# usb_port.net
KiCad netlist of a schematic drawn in Altium Designer
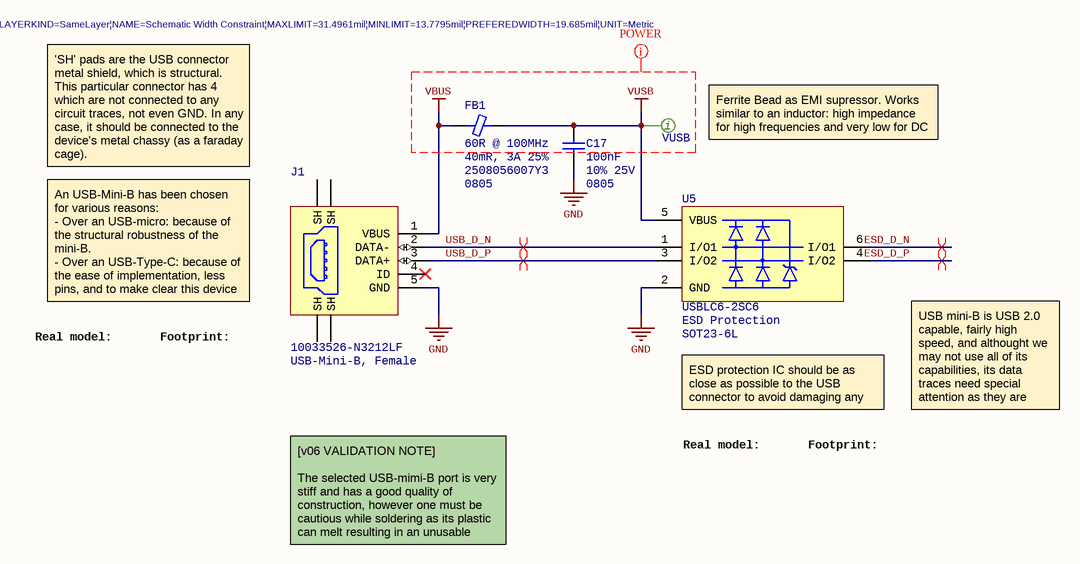
[diagram p0: usb_port.SchDoc]

(export (version "E")
  (design (tool "Eeschema 10.0.6"))
  (components
    (comp (ref "C17")
      (value "100nF")
      (footprint "CAP 0805_2012")
      (description "Ceramic cap size 0805")
      (fields
        (field (name "TOLERANCE") "10% 25V")
        (field (name "PACKAGEDESCRIPTION") "0805")
        (field (name "Comment") "Cap_cer_0805")
      )
      (libsource (lib "tik_handheld_schlib") (part "Cap_cer_0805_100nF_10%"))
    )
    (comp (ref "FB1")
      (value "40mR, 3A 25%")
      (footprint "FER 0805_2012")
      (description "0805, 60Ω, 3A, 25% SMT")
      (fields
        (field (name "DESC") "60R @ 100MHz")
        (field (name "PART") "2508056007Y3")
        (field (name "PACKAGEDESCRIPTION") "0805")
        (field (name "Comment") "Ferrite Bead Chip Fair-Rite 2508056007Y3")
      )
      (libsource (lib "tik_handheld_schlib") (part "Ferrite Bead Chip Fair-Rite 2508056007Y3"))
    )
    (comp (ref "J1")
      (value "USB-MINI-B Female")
      (footprint "FCI USB Type B Mini 10033526-N3212LF")
      (description "USB-MINI-B Female, Manufacturer PN/ID: 10033526-N3212LF")
      (fields
        (field (name "PACKAGEDESCRIPTION") "USB-Mini-B, Female")
        (field (name "PART") "10033526-N3212LF")
      )
      (libsource (lib "tik_handheld_schlib") (part "CON USB-MINI-B Female"))
    )
    (comp (ref "U5")
      (value "IC USBLC6-2SC6 ESD Prot")
      (footprint "SOT-23-6L USBLC6-2SC6")
      (description "Very low capacitance ESD protection")
      (fields
        (field (name "PART") "USBLC6-2SC6")
        (field (name "PACKAGEDESCRIPTION") "SOT23-6L")
        (field (name "TYPE") "ESD Protection")
      )
      (libsource (lib "tik_handheld_schlib") (part "IC USBLC6-2SC6 ESD Prot"))
    )
    (comp (ref "VUSB")
      (value "Test Point Pad dual sided")
      (footprint "TEST POINT PAD")
      (description "Test point - PCB Pad dual sided")
      (libsource (lib "tik_handheld_schlib") (part "Test Point Pad dual sided"))
    )
  )
  (nets
    (net (code "1") (name "/ESD_D_N") (class "Default")
      (node (ref "U5") (pin "6") (pinfunction "I/O1_6") (pintype "passive"))
    )
    (net (code "2") (name "/ESD_D_P") (class "Default")
      (node (ref "U5") (pin "4") (pinfunction "I/O2_4") (pintype "passive"))
    )
    (net (code "3") (name "/USB_D_N") (class "Default")
      (node (ref "J1") (pin "2") (pinfunction "DATA-_2") (pintype "bidirectional"))
      (node (ref "U5") (pin "1") (pinfunction "I/O1_1") (pintype "passive"))
    )
    (net (code "4") (name "/USB_D_P") (class "Default")
      (node (ref "J1") (pin "3") (pinfunction "DATA+_3") (pintype "bidirectional"))
      (node (ref "U5") (pin "3") (pinfunction "I/O2_3") (pintype "passive"))
    )
    (net (code "5") (name "GND") (class "Default")
      (node (ref "C17") (pin "1") (pinfunction "1_1") (pintype "passive"))
      (node (ref "J1") (pin "5") (pinfunction "GND_5") (pintype "power_in"))
      (node (ref "U5") (pin "2") (pinfunction "GND_2") (pintype "passive"))
    )
    (net (code "6") (name "VBUS") (class "Default")
      (node (ref "FB1") (pin "1") (pinfunction "1_1") (pintype "passive"))
      (node (ref "J1") (pin "1") (pinfunction "VBUS_1") (pintype "power_in"))
    )
    (net (code "7") (name "VUSB") (class "Default")
      (node (ref "C17") (pin "2") (pinfunction "2_2") (pintype "passive"))
      (node (ref "FB1") (pin "2") (pinfunction "2_2") (pintype "passive"))
      (node (ref "U5") (pin "5") (pinfunction "VBUS_5") (pintype "passive"))
      (node (ref "VUSB") (pin "1") (pinfunction "1_1") (pintype "passive"))
    )
    (net (code "8") (name "unconnected-(J1-ID-Pad4)") (class "Default")
      (node (ref "J1") (pin "4") (pinfunction "ID_4") (pintype "passive+no_connect"))
    )
    (net (code "9") (name "unconnected-(J1-SH-Pad6)") (class "Default")
      (node (ref "J1") (pin "6") (pinfunction "SH_6") (pintype "passive"))
    )
    (net (code "10") (name "unconnected-(J1-SH-Pad7)") (class "Default")
      (node (ref "J1") (pin "7") (pinfunction "SH_7") (pintype "passive"))
    )
    (net (code "11") (name "unconnected-(J1-SH-Pad8)") (class "Default")
      (node (ref "J1") (pin "8") (pinfunction "SH_8") (pintype "passive"))
    )
    (net (code "12") (name "unconnected-(J1-SH-Pad9)") (class "Default")
      (node (ref "J1") (pin "9") (pinfunction "SH_9") (pintype "passive"))
    )
  )
)
